# Main.net
KiCad netlist of a schematic drawn in Altium Designer
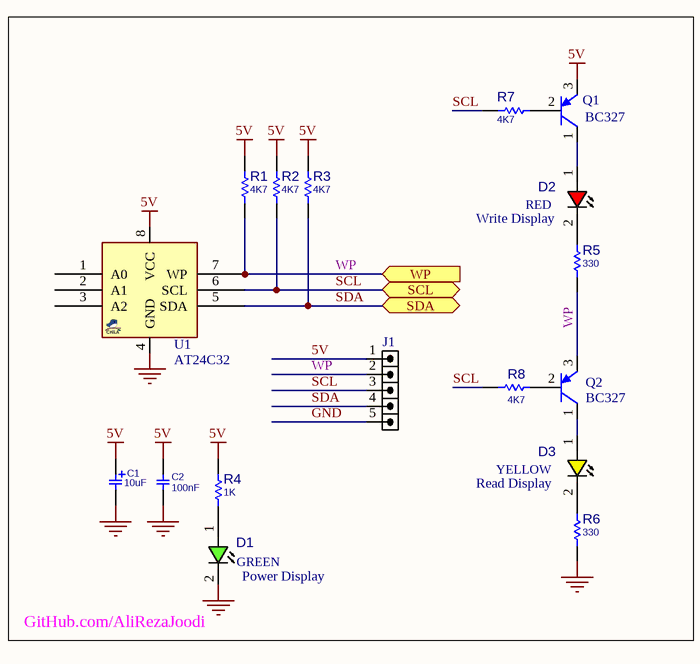
[diagram p0: Main.SchDoc]

(export (version "E")
  (design (tool "Eeschema 10.0.6"))
  (components
    (comp (ref "C1")
      (value "10uF")
      (footprint "C_EL_6X11")
      (description "CAP, THD, ELEC, 10uF, 25V")
      (fields (field (name "MANF") "MANF") (field (name "MANF_P#") "MANF_PART#"))
      (libsource (lib "CapElect_passive") (part "CAP_THD_EL_10u25V"))
    )
    (comp (ref "C2")
      (value "100nF")
      (footprint "C_CER_D3")
      (description "CAP, THD, CER MULTI LAYER,")
      (fields (field (name "MANF_P#") "MANF_PART#") (field (name "MANF") "MANF"))
      (libsource (lib "CapCer_passive") (part "CAP_THD_CERML"))
    )
    (comp (ref "D1")
      (value "GREEN")
      (footprint "LED5MM_GRN")
      (description "LED, THD, 5MM, GREEN")
      (fields (field (name "MANF") "MANF") (field (name "MANF_P#") "MANF_PART#"))
      (libsource (lib "led(diode)") (part "LED_THD_5MM_GRN"))
    )
    (comp (ref "D2")
      (value "RED")
      (footprint "LED5MM_RED")
      (description "LED, THD, 5MM, RED")
      (libsource (lib "led(diode)") (part "LED_THD_5MM_RED"))
    )
    (comp (ref "D3")
      (value "YELLOW")
      (footprint "LED5MM_YLW")
      (description "LED, THD, 5MM, YELLOW")
      (libsource (lib "led(diode)") (part "LED_THD_5MM_YLW"))
    )
    (comp (ref "J1")
      (value "HDR1X5")
      (footprint "HDR_M_1X5")
      (description "CONN, HEADER, Male, pitch: 2.54mm, 5POS")
      (libsource (lib "conn_header_2.54_st") (part "HDR_M_1X5"))
    )
    (comp (ref "Q1")
      (value "BC327")
      (footprint "TO92_3A")
      (description "BJT, PNP, 45v, 0.1A, THD, TO92")
      (fields (field (name "MANF_P#") "BC557") (field (name "MANF") "MULTICOMP"))
      (libsource (lib "transistor_bjt") (part "PNP_BC557_TO92"))
    )
    (comp (ref "Q2")
      (value "BC327")
      (footprint "TO92_3A")
      (description "BJT, PNP, 45v, 0.1A, THD, TO92")
      (fields (field (name "MANF_P#") "BC557") (field (name "MANF") "MULTICOMP"))
      (libsource (lib "transistor_bjt") (part "PNP_BC557_TO92"))
    )
    (comp (ref "R1")
      (value "4K7")
      (footprint "R025W_AX04")
      (description "RESISTOR, THD")
      (fields (field (name "MANF_P#") "RK73H1ETTP4701F") (field (name "MANF") "KOA SPEER"))
      (libsource (lib "passive_thd") (part "RES_THD"))
    )
    (comp (ref "R2")
      (value "4K7")
      (footprint "R025W_AX04")
      (description "RESISTOR, THD")
      (fields (field (name "MANF_P#") "RK73H1ETTP4701F") (field (name "MANF") "KOA SPEER"))
      (libsource (lib "passive_thd") (part "RES_THD"))
    )
    (comp (ref "R3")
      (value "4K7")
      (footprint "R025W_AX04")
      (description "RESISTOR, THD")
      (fields (field (name "MANF_P#") "RK73H1ETTP4701F") (field (name "MANF") "KOA SPEER"))
      (libsource (lib "passive_thd") (part "RES_THD"))
    )
    (comp (ref "R4")
      (value "1K")
      (footprint "R025W_AX04")
      (description "RESISTOR, THD")
      (fields (field (name "MANF_P#") "RK73H1ETTP4701F") (field (name "MANF") "KOA SPEER"))
      (libsource (lib "passive_thd") (part "RES_THD"))
    )
    (comp (ref "R5")
      (value "330")
      (footprint "R025W_AX04")
      (description "RESISTOR, THD")
      (fields (field (name "MANF_P#") "RK73H1ETTP4701F") (field (name "MANF") "KOA SPEER"))
      (libsource (lib "passive_thd") (part "RES_THD"))
    )
    (comp (ref "R6")
      (value "330")
      (footprint "R025W_AX04")
      (description "RESISTOR, THD")
      (fields (field (name "MANF_P#") "RK73H1ETTP4701F") (field (name "MANF") "KOA SPEER"))
      (libsource (lib "passive_thd") (part "RES_THD"))
    )
    (comp (ref "R7")
      (value "4K7")
      (footprint "R025W_AX04")
      (description "RESISTOR, THD")
      (fields (field (name "MANF_P#") "RK73H1ETTP4701F") (field (name "MANF") "KOA SPEER"))
      (libsource (lib "passive_thd") (part "RES_THD"))
    )
    (comp (ref "R8")
      (value "4K7")
      (footprint "R025W_AX04")
      (description "RESISTOR, THD")
      (fields (field (name "MANF_P#") "RK73H1ETTP4701F") (field (name "MANF") "KOA SPEER"))
      (libsource (lib "passive_thd") (part "RES_THD"))
    )
    (comp (ref "U1")
      (value "AT24C32")
      (footprint "DIP_8")
      (description "EEPROM, I2C, 64Kbit (8K X8)")
      (fields (field (name "MANF") "ON") (field (name "MANF_P#") "CAT24C64LI-G"))
      (libsource (lib "memory_eeprom_I2C") (part "EEPROM_I2C_CAT24C64_DIP8"))
    )
  )
  (nets
    (net (code "1") (name "/SCL") (class "Default")
      (node (ref "J1") (pin "3") (pinfunction "3_3") (pintype "passive"))
      (node (ref "R2") (pin "1") (pinfunction "1_1") (pintype "passive"))
      (node (ref "R7") (pin "2") (pinfunction "2_2") (pintype "passive"))
      (node (ref "R8") (pin "2") (pinfunction "2_2") (pintype "passive"))
      (node (ref "U1") (pin "6") (pinfunction "SCL_6") (pintype "passive"))
    )
    (net (code "2") (name "/SDA") (class "Default")
      (node (ref "J1") (pin "4") (pinfunction "4_4") (pintype "passive"))
      (node (ref "R3") (pin "1") (pinfunction "1_1") (pintype "passive"))
      (node (ref "U1") (pin "5") (pinfunction "SDA_5") (pintype "passive"))
    )
    (net (code "3") (name "/WP") (class "Default")
      (node (ref "J1") (pin "2") (pinfunction "2_2") (pintype "passive"))
      (node (ref "Q2") (pin "3") (pinfunction "E_3") (pintype "passive"))
      (node (ref "R1") (pin "1") (pinfunction "1_1") (pintype "passive"))
      (node (ref "R5") (pin "2") (pinfunction "2_2") (pintype "passive"))
      (node (ref "U1") (pin "7") (pinfunction "WP_7") (pintype "passive"))
    )
    (net (code "4") (name "5V") (class "Default")
      (node (ref "C1") (pin "1") (pinfunction "1_1") (pintype "passive"))
      (node (ref "C2") (pin "2") (pinfunction "2_2") (pintype "passive"))
      (node (ref "J1") (pin "1") (pinfunction "1_1") (pintype "passive"))
      (node (ref "Q1") (pin "3") (pinfunction "E_3") (pintype "passive"))
      (node (ref "R1") (pin "2") (pinfunction "2_2") (pintype "passive"))
      (node (ref "R2") (pin "2") (pinfunction "2_2") (pintype "passive"))
      (node (ref "R3") (pin "2") (pinfunction "2_2") (pintype "passive"))
      (node (ref "R4") (pin "2") (pinfunction "2_2") (pintype "passive"))
      (node (ref "U1") (pin "8") (pinfunction "VCC_8") (pintype "passive"))
    )
    (net (code "5") (name "GND") (class "Default")
      (node (ref "C1") (pin "2") (pinfunction "2_2") (pintype "passive"))
      (node (ref "C2") (pin "1") (pinfunction "1_1") (pintype "passive"))
      (node (ref "D1") (pin "2") (pinfunction "CATHODE_2") (pintype "passive"))
      (node (ref "J1") (pin "5") (pinfunction "5_5") (pintype "passive"))
      (node (ref "R6") (pin "2") (pinfunction "2_2") (pintype "passive"))
      (node (ref "U1") (pin "4") (pinfunction "GND_4") (pintype "passive"))
    )
    (net (code "6") (name "Net-(D1-ANODE)") (class "Default")
      (node (ref "D1") (pin "1") (pinfunction "ANODE_1") (pintype "passive"))
      (node (ref "R4") (pin "1") (pinfunction "1_1") (pintype "passive"))
    )
    (net (code "7") (name "Net-(D2-ANODE)") (class "Default")
      (node (ref "D2") (pin "1") (pinfunction "ANODE_1") (pintype "passive"))
      (node (ref "Q1") (pin "1") (pinfunction "C_1") (pintype "passive"))
    )
    (net (code "8") (name "Net-(D2-CATHODE)") (class "Default")
      (node (ref "D2") (pin "2") (pinfunction "CATHODE_2") (pintype "passive"))
      (node (ref "R5") (pin "1") (pinfunction "1_1") (pintype "passive"))
    )
    (net (code "9") (name "Net-(D3-ANODE)") (class "Default")
      (node (ref "D3") (pin "1") (pinfunction "ANODE_1") (pintype "passive"))
      (node (ref "Q2") (pin "1") (pinfunction "C_1") (pintype "passive"))
    )
    (net (code "10") (name "Net-(D3-CATHODE)") (class "Default")
      (node (ref "D3") (pin "2") (pinfunction "CATHODE_2") (pintype "passive"))
      (node (ref "R6") (pin "1") (pinfunction "1_1") (pintype "passive"))
    )
    (net (code "11") (name "Net-(Q1-B)") (class "Default")
      (node (ref "Q1") (pin "2") (pinfunction "B_2") (pintype "passive"))
      (node (ref "R7") (pin "1") (pinfunction "1_1") (pintype "passive"))
    )
    (net (code "12") (name "Net-(Q2-B)") (class "Default")
      (node (ref "Q2") (pin "2") (pinfunction "B_2") (pintype "passive"))
      (node (ref "R8") (pin "1") (pinfunction "1_1") (pintype "passive"))
    )
    (net (code "13") (name "unconnected-(U1-A0-Pad1)") (class "Default")
      (node (ref "U1") (pin "1") (pinfunction "A0_1") (pintype "passive"))
    )
    (net (code "14") (name "unconnected-(U1-A1-Pad2)") (class "Default")
      (node (ref "U1") (pin "2") (pinfunction "A1_2") (pintype "passive"))
    )
    (net (code "15") (name "unconnected-(U1-A2-Pad3)") (class "Default")
      (node (ref "U1") (pin "3") (pinfunction "A2_3") (pintype "passive"))
    )
  )
)
